# 8_LevelShifter.net
KiCad netlist of a schematic drawn in Altium Designer
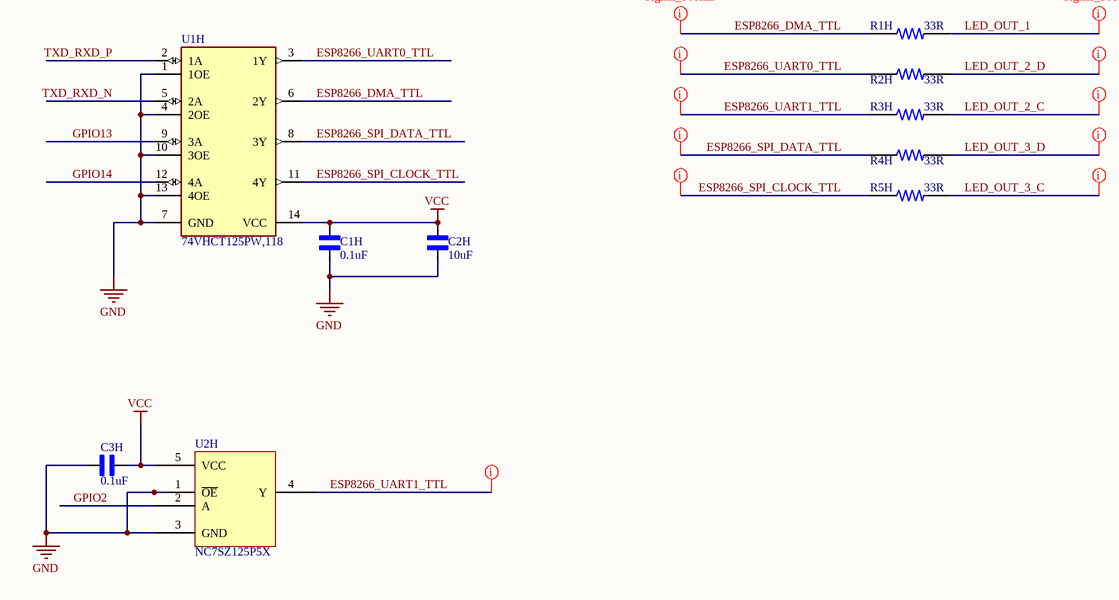
[diagram p0: 8_LevelShifter.SchDoc]

(export (version "E")
  (design (tool "Eeschema 10.0.6"))
  (components
    (comp (ref "C1H")
      (value "0.1uF")
      (footprint "C-0603")
      (description "Ceramic Capacitor 16V 0603 (1608 Metric)")
      (fields (field (name "MP") "C0603C104J4RAC") (field (name "MF") "KEMET"))
      (libsource (lib "") (part "C-0603_1"))
    )
    (comp (ref "C2H")
      (value "10uF")
      (footprint "C-0603")
      (description "Ceramic Capacitor 16V 0603 (1608 Metric)")
      (fields (field (name "MP") "C0603C104J4RAC") (field (name "MF") "KEMET"))
      (libsource (lib "") (part "C-0603_1"))
    )
    (comp (ref "C3H")
      (value "0.1uF")
      (footprint "C-0603")
      (description "Ceramic Capacitor 16V 0603 (1608 Metric)")
      (fields (field (name "MP") "C0603C104J4RAC") (field (name "MF") "KEMET"))
      (libsource (lib "ESP-12F_WLED_IOT_LIPO") (part "C-0603"))
    )
    (comp (ref "R1H")
      (value "33R")
      (footprint "R-0603")
      (description "0603")
      (fields (field (name "MP") "2-1623703-0") (field (name "TOLERANCE") "1%"))
      (libsource (lib "ESP-12F_WLED_IOT_LIPO") (part "R-0603"))
    )
    (comp (ref "R2H")
      (value "33R")
      (footprint "R-0603")
      (description "0603")
      (fields (field (name "MP") "2-1623703-0") (field (name "TOLERANCE") "1%"))
      (libsource (lib "ESP-12F_WLED_IOT_LIPO") (part "R-0603"))
    )
    (comp (ref "R3H")
      (value "33R")
      (footprint "R-0603")
      (description "0603")
      (fields (field (name "MP") "2-1623703-0") (field (name "TOLERANCE") "1%"))
      (libsource (lib "ESP-12F_WLED_IOT_LIPO") (part "R-0603"))
    )
    (comp (ref "R4H")
      (value "33R")
      (footprint "R-0603")
      (description "0603")
      (fields (field (name "MP") "2-1623703-0") (field (name "TOLERANCE") "1%"))
      (libsource (lib "ESP-12F_WLED_IOT_LIPO") (part "R-0603"))
    )
    (comp (ref "R5H")
      (value "33R")
      (footprint "R-0603")
      (description "0603")
      (fields (field (name "MP") "2-1623703-0") (field (name "TOLERANCE") "1%"))
      (libsource (lib "ESP-12F_WLED_IOT_LIPO") (part "R-0603"))
    )
    (comp (ref "U1H")
      (value "74VHCT125PW,118")
      (footprint "Custom-IC:SOP65P640X110-14N")
      (description "Buffer, Non-Inverting 4 Element 1 Bit per Element 3-State Output 14-SOIC")
      (fields (field (name "MP") "74HC125") (field (name "MF") "Nexperia USA"))
      (libsource (lib "ESP-12F_WLED_IOT_LIPO") (part "74VHCT125PW,118"))
    )
    (comp (ref "U2H")
      (value "NC7SZ125P5X")
      (footprint "ON SEMI SC70-5  419AC-01")
      (description "IC BUF NON-INVERT 5.5V SC70-5")
      (fields (field (name "MANUFACTURER") "ON Semiconductor"))
      (libsource (lib "ESP-12F_WLED_IOT_LIPO") (part "ON SEMI NC7SZ125P5X"))
    )
  )
  (nets
    (net (code "1") (name "/ESP8266_DMA_TTL") (class "Default")
      (node (ref "R1H") (pin "1") (pinfunction "1_1") (pintype "passive"))
      (node (ref "U1H") (pin "6") (pinfunction "2Y_6") (pintype "output"))
    )
    (net (code "2") (name "/ESP8266_SPI_CLOCK_TTL") (class "Default")
      (node (ref "R5H") (pin "1") (pinfunction "1_1") (pintype "passive"))
      (node (ref "U1H") (pin "11") (pinfunction "4Y_11") (pintype "output"))
    )
    (net (code "3") (name "/ESP8266_SPI_DATA_TTL") (class "Default")
      (node (ref "R4H") (pin "1") (pinfunction "1_1") (pintype "passive"))
      (node (ref "U1H") (pin "8") (pinfunction "3Y_8") (pintype "output"))
    )
    (net (code "4") (name "/ESP8266_UART0_TTL") (class "Default")
      (node (ref "R2H") (pin "1") (pinfunction "1_1") (pintype "passive"))
      (node (ref "U1H") (pin "3") (pinfunction "1Y_3") (pintype "output"))
    )
    (net (code "5") (name "/ESP8266_UART1_TTL") (class "Default")
      (node (ref "R3H") (pin "1") (pinfunction "1_1") (pintype "passive"))
      (node (ref "U2H") (pin "4") (pinfunction "Y_4") (pintype "passive"))
    )
    (net (code "6") (name "/GPIO2") (class "Default")
      (node (ref "U2H") (pin "2") (pinfunction "A_2") (pintype "passive"))
    )
    (net (code "7") (name "/GPIO13") (class "Default")
      (node (ref "U1H") (pin "9") (pinfunction "3A_9") (pintype "bidirectional"))
    )
    (net (code "8") (name "/GPIO14") (class "Default")
      (node (ref "U1H") (pin "12") (pinfunction "4A_12") (pintype "bidirectional"))
    )
    (net (code "9") (name "/LED_OUT_1") (class "Default")
      (node (ref "R1H") (pin "2") (pinfunction "2_2") (pintype "passive"))
    )
    (net (code "10") (name "/LED_OUT_2_C") (class "Default")
      (node (ref "R3H") (pin "2") (pinfunction "2_2") (pintype "passive"))
    )
    (net (code "11") (name "/LED_OUT_2_D") (class "Default")
      (node (ref "R2H") (pin "2") (pinfunction "2_2") (pintype "passive"))
    )
    (net (code "12") (name "/LED_OUT_3_C") (class "Default")
      (node (ref "R5H") (pin "2") (pinfunction "2_2") (pintype "passive"))
    )
    (net (code "13") (name "/LED_OUT_3_D") (class "Default")
      (node (ref "R4H") (pin "2") (pinfunction "2_2") (pintype "passive"))
    )
    (net (code "14") (name "/TXD_RXD_N") (class "Default")
      (node (ref "U1H") (pin "5") (pinfunction "2A_5") (pintype "bidirectional"))
    )
    (net (code "15") (name "/TXD_RXD_P") (class "Default")
      (node (ref "U1H") (pin "2") (pinfunction "1A_2") (pintype "bidirectional"))
    )
    (net (code "16") (name "GND") (class "Default")
      (node (ref "C1H") (pin "1") (pinfunction "1_1") (pintype "passive"))
      (node (ref "C2H") (pin "1") (pinfunction "1_1") (pintype "passive"))
      (node (ref "C3H") (pin "1") (pinfunction "1_1") (pintype "passive"))
      (node (ref "U1H") (pin "1") (pinfunction "1OE_1") (pintype "passive"))
      (node (ref "U1H") (pin "10") (pinfunction "3OE_10") (pintype "passive"))
      (node (ref "U1H") (pin "13") (pinfunction "4OE_13") (pintype "passive"))
      (node (ref "U1H") (pin "4") (pinfunction "2OE_4") (pintype "passive"))
      (node (ref "U1H") (pin "7") (pinfunction "GND_7") (pintype "power_in"))
      (node (ref "U2H") (pin "1") (pinfunction "~{OE}_1") (pintype "passive"))
      (node (ref "U2H") (pin "3") (pinfunction "GND_3") (pintype "passive"))
    )
    (net (code "17") (name "VCC") (class "Default")
      (node (ref "C1H") (pin "2") (pinfunction "2_2") (pintype "passive"))
      (node (ref "C2H") (pin "2") (pinfunction "2_2") (pintype "passive"))
      (node (ref "C3H") (pin "2") (pinfunction "2_2") (pintype "passive"))
      (node (ref "U1H") (pin "14") (pinfunction "VCC_14") (pintype "power_in"))
      (node (ref "U2H") (pin "5") (pinfunction "VCC_5") (pintype "passive"))
    )
  )
)
